# schematic.net
KiCad netlist of a schematic drawn in EasyEDA
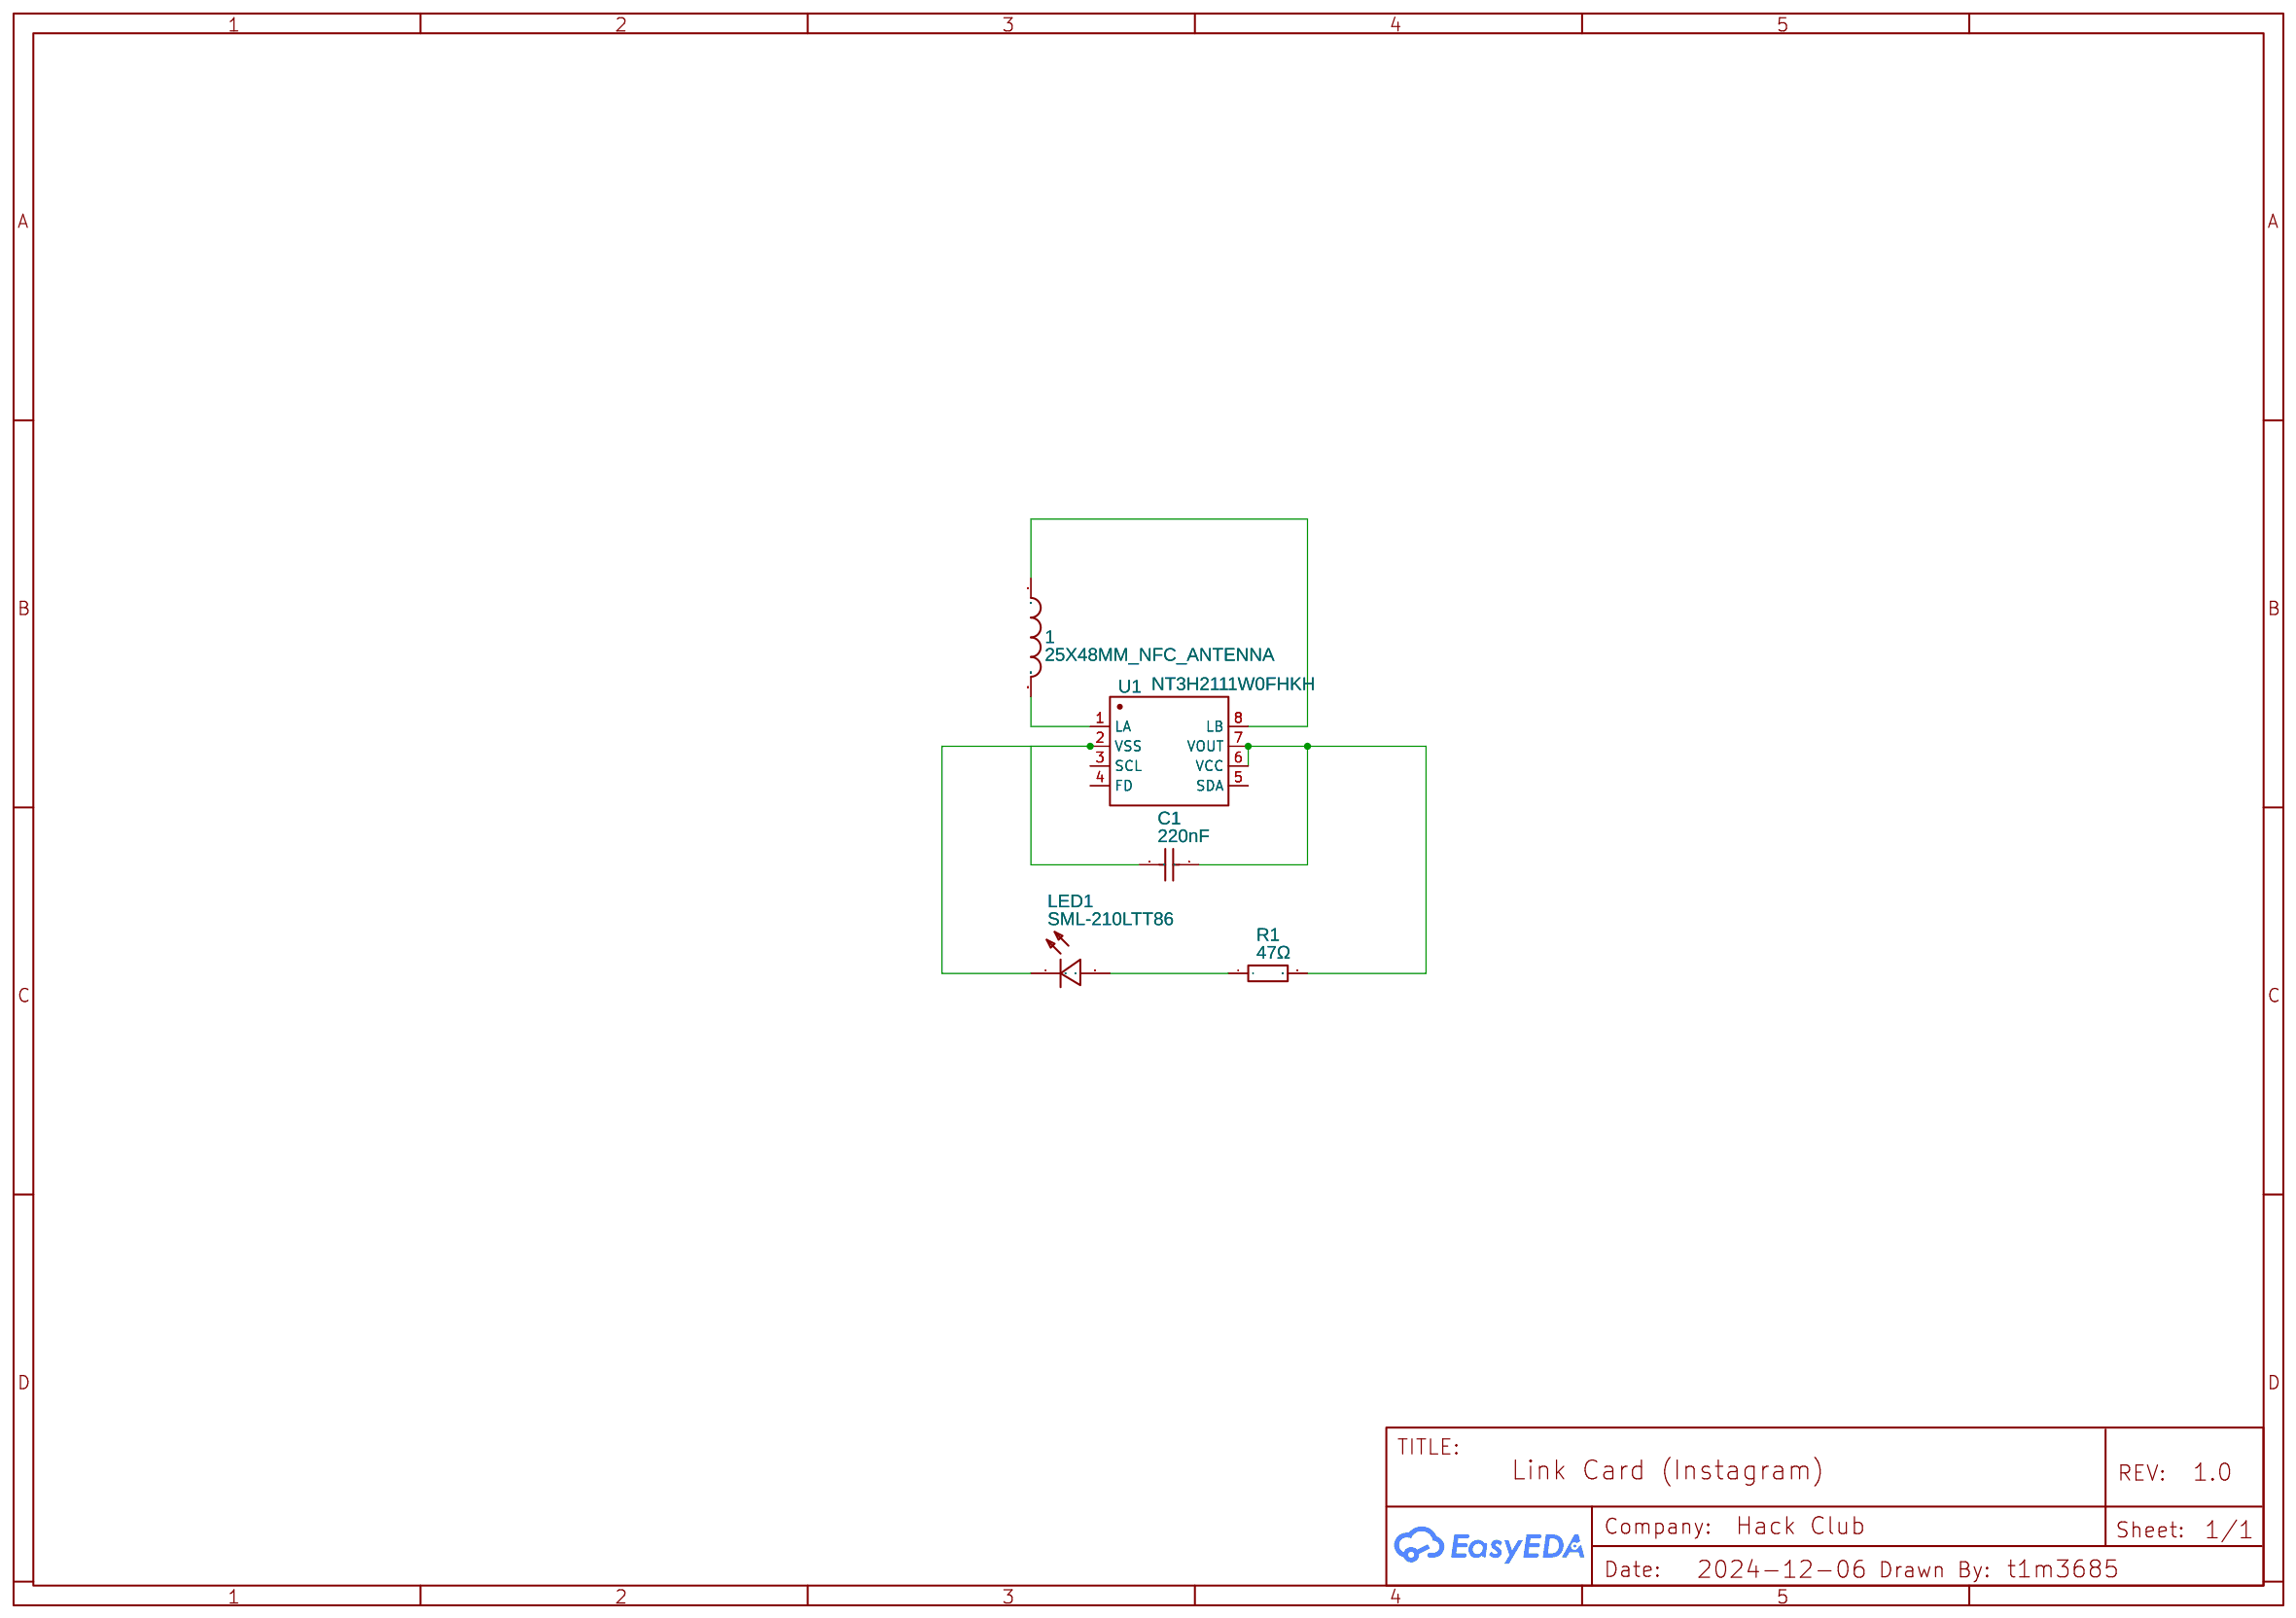
[diagram p0: schematic sheet]

(export (version "E")
  (design (tool "Eeschema 10.0.6"))
  (components
    (comp (ref "1") (value "25X48MM_NFC_ANTENNA") (libsource (lib "") (part "25X48MM_NFC_ANTENNA")))
    (comp (ref "C1")
      (value "220nF")
      (fields
        (field (name "Manufacturer Part") "CL10B224KA8NNNC")
        (field (name "Manufacturer") "SAMSUNG(三星)")
      )
      (libsource (lib "") (part "CL10B224KA8NNNC"))
    )
    (comp (ref "LED1")
      (value "SML-210LTT86")
      (fields (field (name "Manufacturer") "ROHM(罗姆)"))
      (libsource (lib "") (part "SML-210LTT86"))
    )
    (comp (ref "R1")
      (value "47Ω")
      (fields
        (field (name "Manufacturer Part") "0603WAF470JT5E")
        (field (name "Manufacturer") "UNI-ROYAL(厚声)")
      )
      (libsource (lib "") (part "0603WAF470JT5E"))
    )
    (comp (ref "U1")
      (value "NT3H2111W0FHKH")
      (fields (field (name "Manufacturer") "NXP(恩智浦)"))
      (libsource (lib "") (part "NT3H2111W0FHKH"))
    )
  )
  (nets
    (net (code "1") (name "Net-(LED1-A)") (class "Default")
      (node (ref "LED1") (pin "2") (pinfunction "A_2") (pintype "unspecified"))
      (node (ref "R1") (pin "1") (pinfunction "1_1") (pintype "input"))
    )
    (net (code "2") (name "Net-(LED1-C)") (class "Default")
      (node (ref "C1") (pin "1") (pinfunction "1_1") (pintype "input"))
      (node (ref "LED1") (pin "1") (pinfunction "C_1") (pintype "unspecified"))
      (node (ref "U1") (pin "2") (pinfunction "VSS_2") (pintype "unspecified"))
    )
    (net (code "3") (name "Net-(U1-LA)") (class "Default")
      (node (ref "1") (pin "P$2") (pinfunction "P$2_P$2") (pintype "bidirectional"))
      (node (ref "U1") (pin "1") (pinfunction "LA_1") (pintype "unspecified"))
    )
    (net (code "4") (name "Net-(U1-LB)") (class "Default")
      (node (ref "1") (pin "P$1") (pinfunction "P$1_P$1") (pintype "bidirectional"))
      (node (ref "U1") (pin "8") (pinfunction "LB_8") (pintype "unspecified"))
    )
    (net (code "5") (name "Net-(U1-VCC)") (class "Default")
      (node (ref "C1") (pin "2") (pinfunction "2_2") (pintype "input"))
      (node (ref "R1") (pin "2") (pinfunction "2_2") (pintype "input"))
      (node (ref "U1") (pin "6") (pinfunction "VCC_6") (pintype "unspecified"))
      (node (ref "U1") (pin "7") (pinfunction "VOUT_7") (pintype "unspecified"))
    )
    (net (code "6") (name "unconnected-(U1-FD-Pad4)") (class "Default")
      (node (ref "U1") (pin "4") (pinfunction "FD_4") (pintype "unspecified"))
    )
    (net (code "7") (name "unconnected-(U1-SCL-Pad3)") (class "Default")
      (node (ref "U1") (pin "3") (pinfunction "SCL_3") (pintype "unspecified"))
    )
    (net (code "8") (name "unconnected-(U1-SDA-Pad5)") (class "Default")
      (node (ref "U1") (pin "5") (pinfunction "SDA_5") (pintype "unspecified"))
    )
  )
)
